# pcb.net
KiCad netlist of a schematic drawn in EAGLE
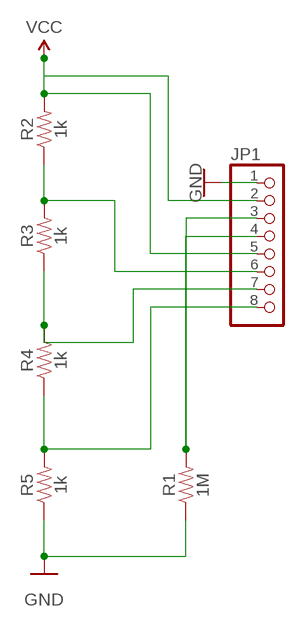
[diagram p0: schematic, sheet 1]

(export (version "E")
  (design (tool "Eeschema 10.0.6"))
  (components
    (comp (ref "JP1")
      (value "PINHD-1X8-3.5MM")
      (footprint "eagle-import:1X08-3.5MM")
      (libsource (lib "eagle-import") (part "PINHD-1X8-3.5MM"))
    )
    (comp (ref "R1")
      (value "1M")
      (footprint "eagle-import:AXIAL-0.3")
      (libsource (lib "eagle-import") (part "1MOHM-HORIZ-1/6W-5%"))
    )
    (comp (ref "R2")
      (value "1k")
      (footprint "eagle-import:AXIAL-0.3")
      (libsource (lib "eagle-import") (part "1KOHM-HORIZ-1/4W-5%"))
    )
    (comp (ref "R3")
      (value "1k")
      (footprint "eagle-import:AXIAL-0.3")
      (libsource (lib "eagle-import") (part "1KOHM-HORIZ-1/4W-5%"))
    )
    (comp (ref "R4")
      (value "1k")
      (footprint "eagle-import:AXIAL-0.3")
      (libsource (lib "eagle-import") (part "1KOHM-HORIZ-1/4W-5%"))
    )
    (comp (ref "R5")
      (value "1k")
      (footprint "eagle-import:AXIAL-0.3")
      (libsource (lib "eagle-import") (part "1KOHM-HORIZ-1/4W-5%"))
    )
  )
  (nets
    (net (code "1") (name "GND") (class "Default")
      (node (ref "JP1") (pin "1") (pinfunction "1_1") (pintype "passive"))
      (node (ref "R1") (pin "P$1") (pinfunction "1_P$1") (pintype "passive"))
      (node (ref "R5") (pin "P$1") (pinfunction "1_P$1") (pintype "passive"))
    )
    (net (code "2") (name "Net-(R1-2)") (class "Default")
      (node (ref "JP1") (pin "3") (pinfunction "3_3") (pintype "passive"))
      (node (ref "JP1") (pin "4") (pinfunction "4_4") (pintype "passive"))
      (node (ref "R1") (pin "P$2") (pinfunction "2_P$2") (pintype "passive"))
    )
    (net (code "3") (name "Net-(R2-1)") (class "Default")
      (node (ref "JP1") (pin "6") (pinfunction "6_6") (pintype "passive"))
      (node (ref "R2") (pin "P$1") (pinfunction "1_P$1") (pintype "passive"))
      (node (ref "R3") (pin "P$2") (pinfunction "2_P$2") (pintype "passive"))
    )
    (net (code "4") (name "Net-(R3-1)") (class "Default")
      (node (ref "JP1") (pin "7") (pinfunction "7_7") (pintype "passive"))
      (node (ref "R3") (pin "P$1") (pinfunction "1_P$1") (pintype "passive"))
      (node (ref "R4") (pin "P$2") (pinfunction "2_P$2") (pintype "passive"))
    )
    (net (code "5") (name "Net-(R4-1)") (class "Default")
      (node (ref "JP1") (pin "8") (pinfunction "8_8") (pintype "passive"))
      (node (ref "R4") (pin "P$1") (pinfunction "1_P$1") (pintype "passive"))
      (node (ref "R5") (pin "P$2") (pinfunction "2_P$2") (pintype "passive"))
    )
    (net (code "6") (name "VCC") (class "Default")
      (node (ref "JP1") (pin "2") (pinfunction "2_2") (pintype "passive"))
      (node (ref "JP1") (pin "5") (pinfunction "5_5") (pintype "passive"))
      (node (ref "R2") (pin "P$2") (pinfunction "2_P$2") (pintype "passive"))
    )
  )
)
